# fc_power_board.net
KiCad netlist of a schematic drawn in EAGLE
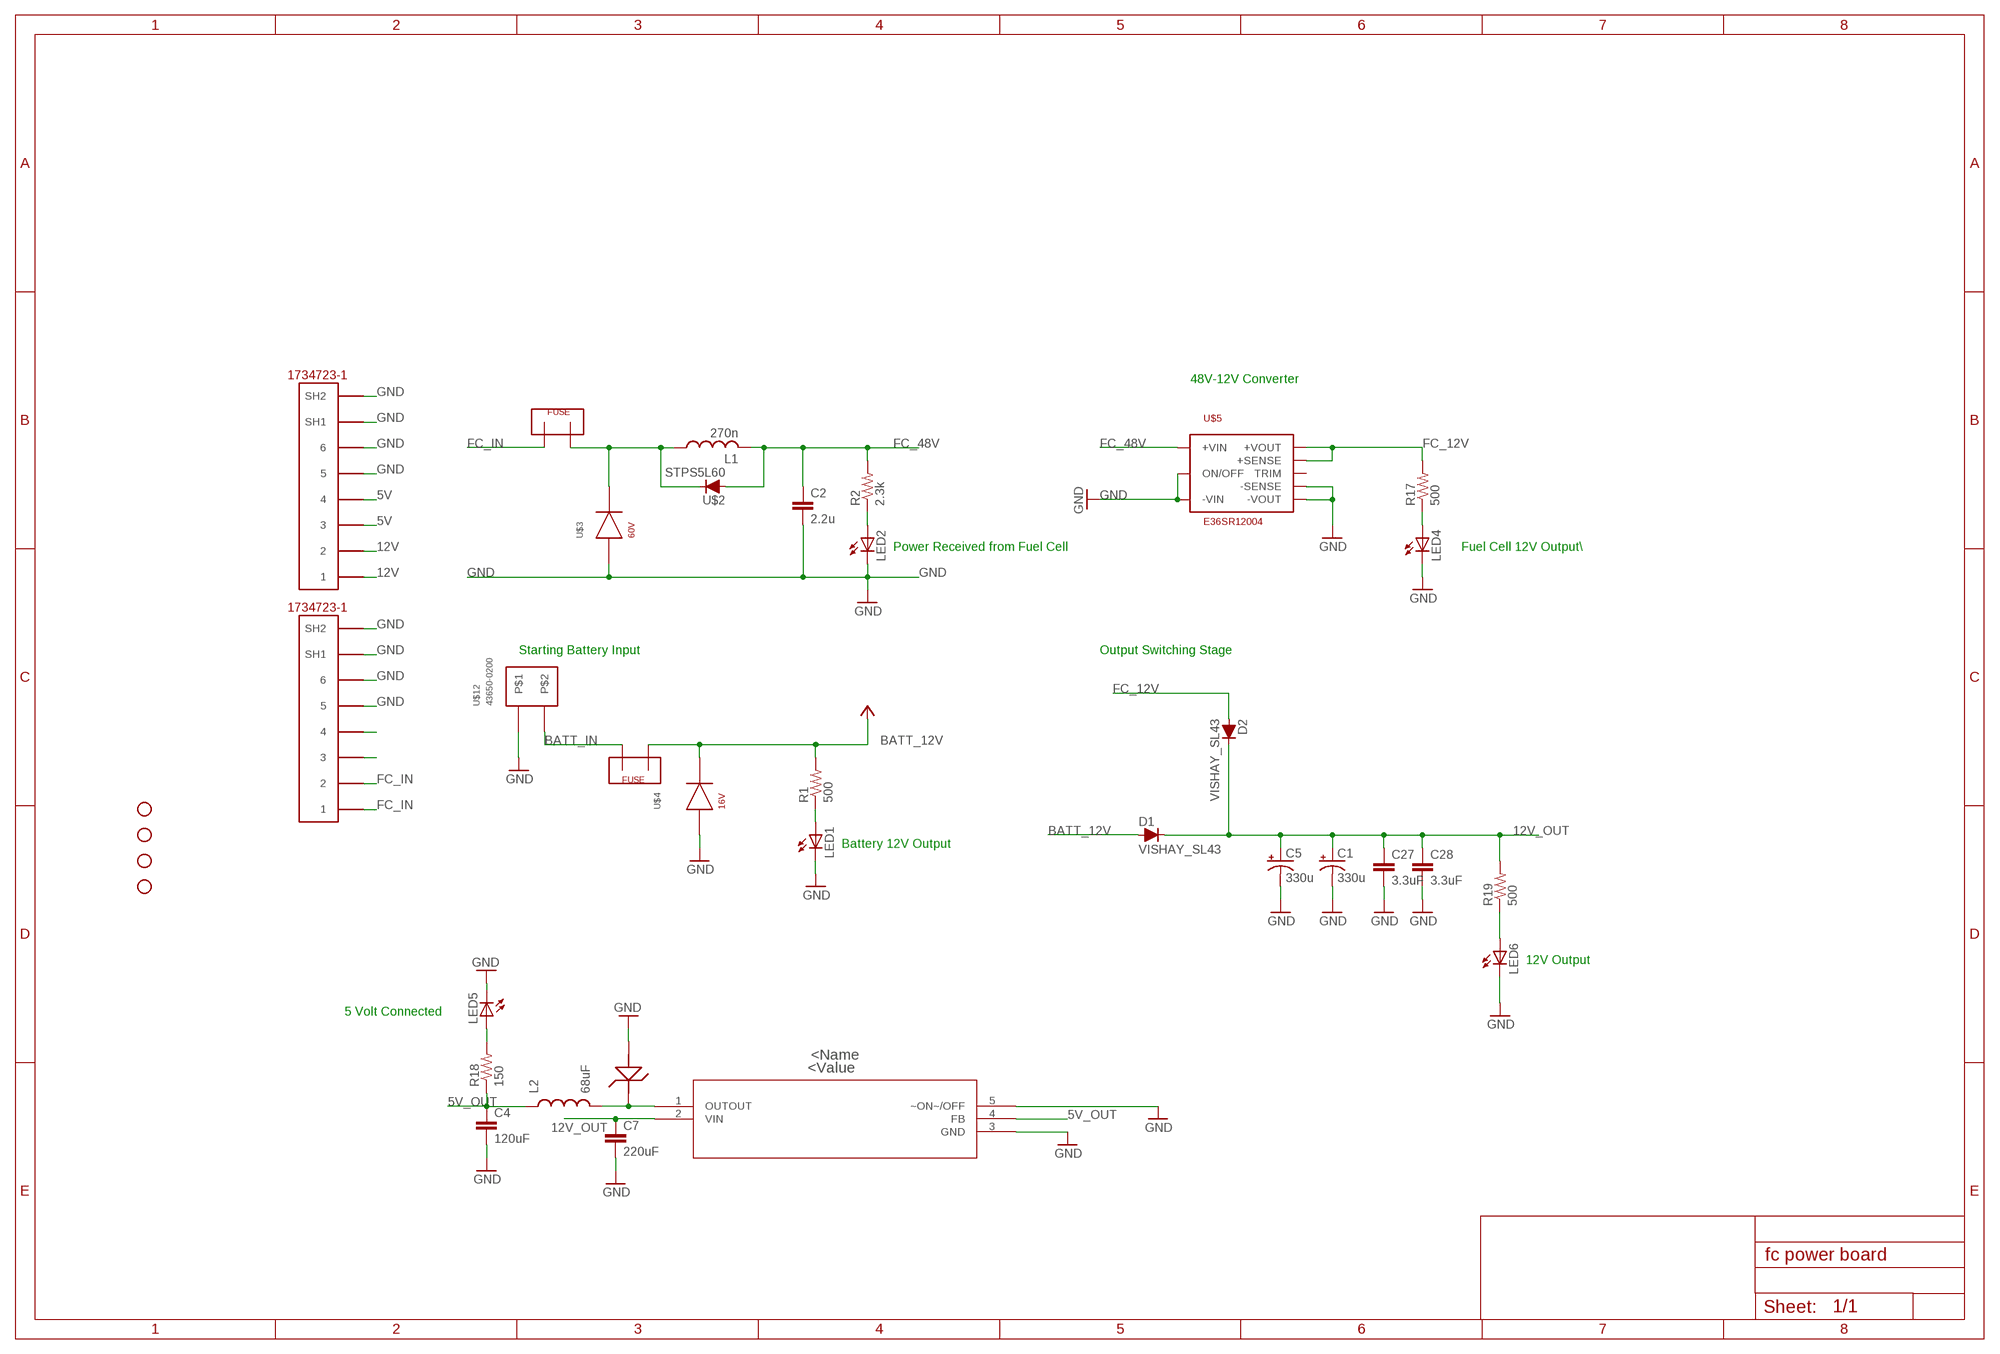
[diagram p0: schematic, sheet 1]

(export (version "E")
  (design (tool "Eeschema 10.0.6"))
  (components
    (comp (ref "C1")
      (value "330u")
      (footprint "eagle-import:PANASONIC_E")
      (libsource (lib "eagle-import") (part "CAP_POLE"))
    )
    (comp (ref "C2")
      (value "2.2u")
      (footprint "eagle-import:C1210")
      (libsource (lib "eagle-import") (part "C-EUC1210"))
    )
    (comp (ref "C4")
      (value "120uF")
      (footprint "eagle-import:0805")
      (libsource (lib "eagle-import") (part "CAP0805"))
    )
    (comp (ref "C5")
      (value "330u")
      (footprint "eagle-import:PANASONIC_E")
      (libsource (lib "eagle-import") (part "CAP_POLE"))
    )
    (comp (ref "C7")
      (value "220uF")
      (footprint "eagle-import:0805")
      (libsource (lib "eagle-import") (part "CAP0805"))
    )
    (comp (ref "C27")
      (value "3.3uF")
      (footprint "eagle-import:C0805K")
      (libsource (lib "eagle-import") (part "C-EUC0805K"))
    )
    (comp (ref "C28")
      (value "3.3uF")
      (footprint "eagle-import:C0805K")
      (libsource (lib "eagle-import") (part "C-EUC0805K"))
    )
    (comp (ref "D1")
      (value "VISHAY_SL43")
      (footprint "eagle-import:DO-214AB_SMC")
      (libsource (lib "eagle-import") (part "VISHAY_SL43"))
    )
    (comp (ref "D2")
      (value "VISHAY_SL43")
      (footprint "eagle-import:DO-214AB_SMC")
      (libsource (lib "eagle-import") (part "VISHAY_SL43"))
    )
    (comp (ref "L1")
      (value "270n")
      (footprint "eagle-import:L3225P")
      (libsource (lib "eagle-import") (part "L-USL3225P"))
    )
    (comp (ref "L2")
      (value "68uF")
      (footprint "eagle-import:0805")
      (libsource (lib "eagle-import") (part "INDUCTOR0805"))
    )
    (comp (ref "LED1")
      (value "LED1206")
      (footprint "eagle-import:LED-1206")
      (libsource (lib "eagle-import") (part "LED1206"))
    )
    (comp (ref "LED2")
      (value "LED1206")
      (footprint "eagle-import:LED-1206")
      (libsource (lib "eagle-import") (part "LED1206"))
    )
    (comp (ref "LED4")
      (value "LED1206")
      (footprint "eagle-import:LED-1206")
      (libsource (lib "eagle-import") (part "LED1206"))
    )
    (comp (ref "LED5")
      (value "LED1206")
      (footprint "eagle-import:LED-1206")
      (libsource (lib "eagle-import") (part "LED1206"))
    )
    (comp (ref "LED6")
      (value "LED1206")
      (footprint "eagle-import:LED-1206")
      (libsource (lib "eagle-import") (part "LED1206"))
    )
    (comp (ref "R1")
      (value "500")
      (footprint "eagle-import:M0805")
      (libsource (lib "eagle-import") (part "R-US_M0805"))
    )
    (comp (ref "R2")
      (value "2.3k")
      (footprint "eagle-import:M0805")
      (libsource (lib "eagle-import") (part "R-US_M0805"))
    )
    (comp (ref "R17")
      (value "500")
      (footprint "eagle-import:M0805")
      (libsource (lib "eagle-import") (part "R-US_M0805"))
    )
    (comp (ref "R18")
      (value "150")
      (footprint "eagle-import:M0805")
      (libsource (lib "eagle-import") (part "R-US_M0805"))
    )
    (comp (ref "R19")
      (value "500")
      (footprint "eagle-import:M0805")
      (libsource (lib "eagle-import") (part "R-US_M0805"))
    )
    (comp (ref "STANDOFF1")
      (value "STAND-OFF")
      (footprint "eagle-import:STAND-OFF")
      (libsource (lib "eagle-import") (part "STAND-OFF"))
    )
    (comp (ref "STANDOFF2")
      (value "STAND-OFF")
      (footprint "eagle-import:STAND-OFF")
      (libsource (lib "eagle-import") (part "STAND-OFF"))
    )
    (comp (ref "STANDOFF3")
      (value "STAND-OFF")
      (footprint "eagle-import:STAND-OFF")
      (libsource (lib "eagle-import") (part "STAND-OFF"))
    )
    (comp (ref "STANDOFF4")
      (value "STAND-OFF")
      (footprint "eagle-import:STAND-OFF")
      (libsource (lib "eagle-import") (part "STAND-OFF"))
    )
    (comp (ref "U$2")
      (value "STPS5L60")
      (footprint "eagle-import:STM_SMC")
      (libsource (lib "eagle-import") (part "STPS5L60"))
    )
    (comp (ref "U$3")
      (value "SMBJ60CA")
      (footprint "eagle-import:.277X.089")
      (libsource (lib "eagle-import") (part "SMBJ60CA"))
    )
    (comp (ref "U$4")
      (value "SMAJ16CA")
      (footprint "eagle-import:.25X.07")
      (libsource (lib "eagle-import") (part "SMAJ16CA"))
    )
    (comp (ref "U$5")
      (value "E36SR12004")
      (footprint "eagle-import:2.30X0.90X0.34")
      (libsource (lib "eagle-import") (part "E36SR12004"))
    )
    (comp (ref "U$6")
      (value "5555140-6")
      (footprint "eagle-import:1734723-1_RJ11")
      (libsource (lib "eagle-import") (part "5555140-6"))
    )
    (comp (ref "U$7")
      (value "FUSEMINI-BLADE")
      (footprint "eagle-import:MINI-BLADE-FUSE")
      (libsource (lib "eagle-import") (part "FUSEMINI-BLADE"))
    )
    (comp (ref "U$8")
      (value "LM2595T-5.0")
      (footprint "eagle-import:T05D")
      (fields
        (field (name "MANUFACTURER_PART_NUMBER") "LM2595T50")
        (field (name "COPYRIGHT") "Copyright C 2015 Accelerated Designs. All rights reserved")
      )
      (libsource (lib "eagle-import") (part "LM2595T-5.0"))
    )
    (comp (ref "U$9")
      (value "MURS120T3G")
      (footprint "eagle-import:MURS120T3G")
      (libsource (lib "eagle-import") (part "MURS120T3G"))
    )
    (comp (ref "U$10")
      (value "FUSEMINI-BLADE")
      (footprint "eagle-import:MINI-BLADE-FUSE")
      (libsource (lib "eagle-import") (part "FUSEMINI-BLADE"))
    )
    (comp (ref "U$11")
      (value "5555140-6")
      (footprint "eagle-import:1734723-1_RJ11")
      (libsource (lib "eagle-import") (part "5555140-6"))
    )
    (comp (ref "U$12")
      (value "43650-0200")
      (footprint "eagle-import:43650-0200")
      (libsource (lib "eagle-import") (part "43650-0200"))
    )
  )
  (nets
    (net (code "1") (name "+5V") (class "Default")
      (node (ref "D1") (pin "A") (pinfunction "A_A") (pintype "passive"))
      (node (ref "R1") (pin "2") (pinfunction "2_2") (pintype "passive"))
      (node (ref "U$10") (pin "OUT") (pinfunction "OUT_OUT") (pintype "bidirectional"))
      (node (ref "U$4") (pin "CATHODE") (pinfunction "CATHODE_CATHODE") (pintype "bidirectional"))
    )
    (net (code "2") (name "/5V") (class "Default")
      (node (ref "U$11") (pin "3") (pinfunction "3_3") (pintype "bidirectional"))
      (node (ref "U$11") (pin "4") (pinfunction "4_4") (pintype "bidirectional"))
    )
    (net (code "3") (name "/5V_OUT") (class "Default")
      (node (ref "C4") (pin "1") (pinfunction "1_1") (pintype "passive"))
      (node (ref "L2") (pin "1") (pinfunction "1_1") (pintype "passive"))
      (node (ref "R18") (pin "1") (pinfunction "1_1") (pintype "passive"))
      (node (ref "U$8") (pin "4") (pinfunction "FB_4") (pintype "passive"))
    )
    (net (code "4") (name "/12V") (class "Default")
      (node (ref "U$11") (pin "1") (pinfunction "1_1") (pintype "bidirectional"))
      (node (ref "U$11") (pin "2") (pinfunction "2_2") (pintype "bidirectional"))
    )
    (net (code "5") (name "/12V_OUT") (class "Default")
      (node (ref "C1") (pin "+") (pinfunction "+_+") (pintype "passive"))
      (node (ref "C27") (pin "1") (pinfunction "1_1") (pintype "passive"))
      (node (ref "C28") (pin "1") (pinfunction "1_1") (pintype "passive"))
      (node (ref "C5") (pin "+") (pinfunction "+_+") (pintype "passive"))
      (node (ref "C7") (pin "1") (pinfunction "1_1") (pintype "passive"))
      (node (ref "D1") (pin "C") (pinfunction "C_C") (pintype "passive"))
      (node (ref "D2") (pin "C") (pinfunction "C_C") (pintype "passive"))
      (node (ref "R19") (pin "2") (pinfunction "2_2") (pintype "passive"))
      (node (ref "U$8") (pin "2") (pinfunction "VIN_2") (pintype "input"))
    )
    (net (code "6") (name "/BATT_IN") (class "Default")
      (node (ref "U$10") (pin "IN") (pinfunction "IN_IN") (pintype "bidirectional"))
      (node (ref "U$12") (pin "P$1") (pinfunction "P$2_P$1") (pintype "bidirectional"))
    )
    (net (code "7") (name "/FC_12V") (class "Default")
      (node (ref "D2") (pin "A") (pinfunction "A_A") (pintype "passive"))
      (node (ref "R17") (pin "2") (pinfunction "2_2") (pintype "passive"))
      (node (ref "U$5") (pin "P$7") (pinfunction "+SENSE_P$7") (pintype "input"))
      (node (ref "U$5") (pin "P$8") (pinfunction "+VOUT_P$8") (pintype "power_in"))
    )
    (net (code "8") (name "/FC_48V") (class "Default")
      (node (ref "C2") (pin "1") (pinfunction "1_1") (pintype "passive"))
      (node (ref "L1") (pin "2") (pinfunction "2_2") (pintype "passive"))
      (node (ref "R2") (pin "2") (pinfunction "2_2") (pintype "passive"))
      (node (ref "U$2") (pin "A") (pinfunction "A_A") (pintype "passive"))
      (node (ref "U$5") (pin "P$1") (pinfunction "+VIN_P$1") (pintype "power_in"))
    )
    (net (code "9") (name "/FC_IN") (class "Default")
      (node (ref "U$6") (pin "1") (pinfunction "1_1") (pintype "bidirectional"))
      (node (ref "U$6") (pin "2") (pinfunction "2_2") (pintype "bidirectional"))
      (node (ref "U$7") (pin "OUT") (pinfunction "OUT_OUT") (pintype "bidirectional"))
    )
    (net (code "10") (name "GND") (class "Default")
      (node (ref "C1") (pin "-") (pinfunction "-_-") (pintype "passive"))
      (node (ref "C2") (pin "2") (pinfunction "2_2") (pintype "passive"))
      (node (ref "C27") (pin "2") (pinfunction "2_2") (pintype "passive"))
      (node (ref "C28") (pin "2") (pinfunction "2_2") (pintype "passive"))
      (node (ref "C4") (pin "2") (pinfunction "2_2") (pintype "passive"))
      (node (ref "C5") (pin "-") (pinfunction "-_-") (pintype "passive"))
      (node (ref "C7") (pin "2") (pinfunction "2_2") (pintype "passive"))
      (node (ref "LED1") (pin "C") (pinfunction "C_C") (pintype "passive"))
      (node (ref "LED2") (pin "C") (pinfunction "C_C") (pintype "passive"))
      (node (ref "LED4") (pin "C") (pinfunction "C_C") (pintype "passive"))
      (node (ref "LED5") (pin "C") (pinfunction "C_C") (pintype "passive"))
      (node (ref "LED6") (pin "C") (pinfunction "C_C") (pintype "passive"))
      (node (ref "U$11") (pin "5") (pinfunction "5_5") (pintype "bidirectional"))
      (node (ref "U$11") (pin "6") (pinfunction "6_6") (pintype "bidirectional"))
      (node (ref "U$11") (pin "SH1") (pinfunction "SH1_SH1") (pintype "bidirectional"))
      (node (ref "U$11") (pin "SH2") (pinfunction "SH2_SH2") (pintype "bidirectional"))
      (node (ref "U$12") (pin "P$2") (pinfunction "P$1_P$2") (pintype "bidirectional"))
      (node (ref "U$3") (pin "ANODE") (pinfunction "ANODE_ANODE") (pintype "bidirectional"))
      (node (ref "U$4") (pin "ANODE") (pinfunction "ANODE_ANODE") (pintype "bidirectional"))
      (node (ref "U$5") (pin "P$2") (pinfunction "ON/OFF_P$2") (pintype "bidirectional"))
      (node (ref "U$5") (pin "P$3") (pinfunction "-VIN_P$3") (pintype "power_in"))
      (node (ref "U$5") (pin "P$4") (pinfunction "-VOUT_P$4") (pintype "power_in"))
      (node (ref "U$5") (pin "P$5") (pinfunction "-SENSE_P$5") (pintype "input"))
      (node (ref "U$6") (pin "5") (pinfunction "5_5") (pintype "bidirectional"))
      (node (ref "U$6") (pin "6") (pinfunction "6_6") (pintype "bidirectional"))
      (node (ref "U$6") (pin "SH1") (pinfunction "SH1_SH1") (pintype "bidirectional"))
      (node (ref "U$6") (pin "SH2") (pinfunction "SH2_SH2") (pintype "bidirectional"))
      (node (ref "U$8") (pin "3") (pinfunction "GND_3") (pintype "passive"))
      (node (ref "U$8") (pin "5") (pinfunction "~{ON}/OFF_5") (pintype "passive"))
      (node (ref "U$9") (pin "P$2") (pinfunction "PIN1_P$2") (pintype "bidirectional"))
    )
    (net (code "11") (name "Net-(L1-Pad1)") (class "Default")
      (node (ref "L1") (pin "1") (pinfunction "1_1") (pintype "passive"))
      (node (ref "U$2") (pin "C") (pinfunction "C_C") (pintype "passive"))
      (node (ref "U$3") (pin "CATHODE") (pinfunction "CATHODE_CATHODE") (pintype "bidirectional"))
      (node (ref "U$7") (pin "IN") (pinfunction "IN_IN") (pintype "bidirectional"))
    )
    (net (code "12") (name "Net-(LED1-PadA)") (class "Default")
      (node (ref "LED1") (pin "A") (pinfunction "A_A") (pintype "passive"))
      (node (ref "R1") (pin "1") (pinfunction "1_1") (pintype "passive"))
    )
    (net (code "13") (name "Net-(LED2-PadA)") (class "Default")
      (node (ref "LED2") (pin "A") (pinfunction "A_A") (pintype "passive"))
      (node (ref "R2") (pin "1") (pinfunction "1_1") (pintype "passive"))
    )
    (net (code "14") (name "Net-(LED4-PadA)") (class "Default")
      (node (ref "LED4") (pin "A") (pinfunction "A_A") (pintype "passive"))
      (node (ref "R17") (pin "1") (pinfunction "1_1") (pintype "passive"))
    )
    (net (code "15") (name "Net-(LED5-PadA)") (class "Default")
      (node (ref "LED5") (pin "A") (pinfunction "A_A") (pintype "passive"))
      (node (ref "R18") (pin "2") (pinfunction "2_2") (pintype "passive"))
    )
    (net (code "16") (name "Net-(LED6-PadA)") (class "Default")
      (node (ref "LED6") (pin "A") (pinfunction "A_A") (pintype "passive"))
      (node (ref "R19") (pin "1") (pinfunction "1_1") (pintype "passive"))
    )
    (net (code "17") (name "Net-(U$8-OUTOUT)") (class "Default")
      (node (ref "L2") (pin "2") (pinfunction "2_2") (pintype "passive"))
      (node (ref "U$8") (pin "1") (pinfunction "OUTOUT_1") (pintype "output"))
      (node (ref "U$9") (pin "P$1") (pinfunction "P$2_P$1") (pintype "bidirectional"))
    )
    (net (code "18") (name "unconnected-(U$5-TRIM-PadP$6)") (class "Default")
      (node (ref "U$5") (pin "P$6") (pinfunction "TRIM_P$6") (pintype "bidirectional"))
    )
    (net (code "19") (name "unconnected-(U$6-Pad3)") (class "Default")
      (node (ref "U$6") (pin "3") (pinfunction "3_3") (pintype "bidirectional"))
    )
    (net (code "20") (name "unconnected-(U$6-Pad4)") (class "Default")
      (node (ref "U$6") (pin "4") (pinfunction "4_4") (pintype "bidirectional"))
    )
  )
)
